# pca10040_sheet3_buttons_and_leds.net
KiCad netlist of a schematic drawn in Altium Designer
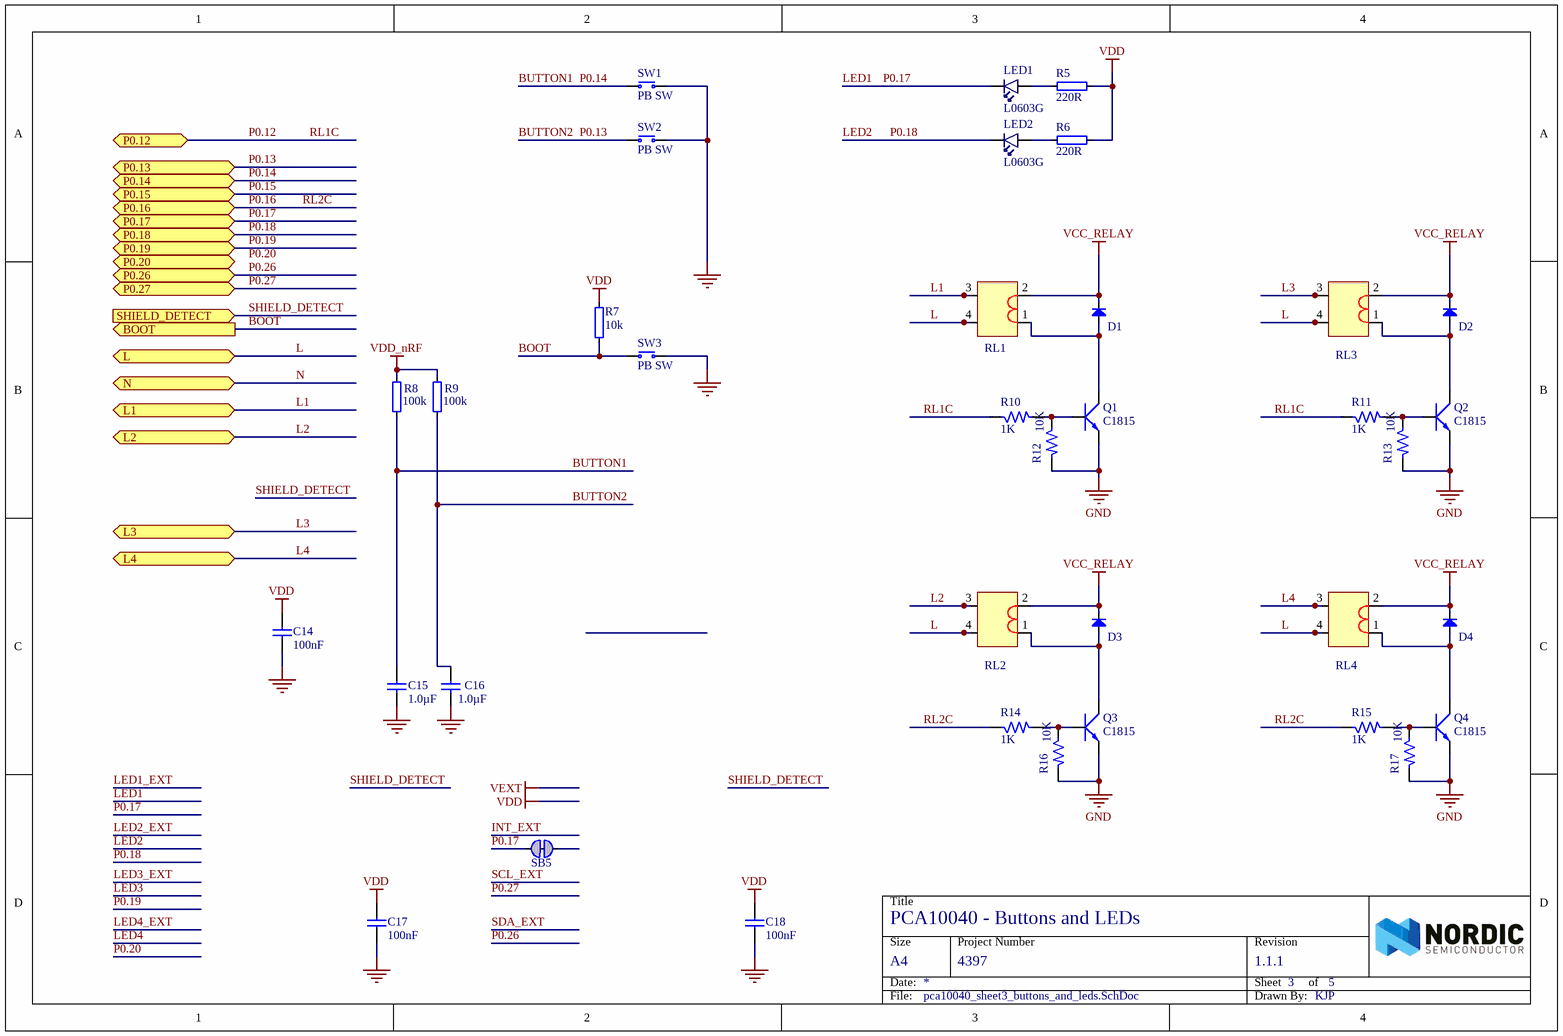
[diagram p0: pca10040_sheet3_buttons_and_leds.SchDoc]

(export (version "E")
  (design (tool "Eeschema 10.0.6"))
  (components
    (comp (ref "C14")
      (value "100nF")
      (footprint "CAPC1005X04L")
      (description "Capacitor, X7R, ±10%")
      (fields (field (name "PART NUMBER") "C0402-100n") (field (name "PUBLISHER") "Nordic Semiconductor"))
      (libsource (lib "Nordic Passive DB") (part "CAP"))
    )
    (comp (ref "C15")
      (value "1.0µF")
      (footprint "CAPC1608X06L")
      (description "Capacitor, X5R, ±5%")
      (fields (field (name "PART NUMBER") "C0402-1µ0") (field (name "PUBLISHER") "Nordic Semiconductor"))
      (libsource (lib "Nordic Passive DB") (part "CAP"))
    )
    (comp (ref "C16")
      (value "1.0µF")
      (footprint "CAPC1608X06L")
      (description "Capacitor, X5R, ±5%")
      (fields (field (name "PART NUMBER") "C0402-1µ0") (field (name "PUBLISHER") "Nordic Semiconductor"))
      (libsource (lib "Nordic Passive DB") (part "CAP"))
    )
    (comp (ref "C17")
      (value "100nF")
      (footprint "CAPC1005X04L")
      (description "Capacitor, X7R, ±10%")
      (fields (field (name "PART NUMBER") "C0402-100n") (field (name "PUBLISHER") "Nordic Semiconductor"))
      (libsource (lib "Nordic Passive DB") (part "CAP"))
    )
    (comp (ref "C18")
      (value "100nF")
      (footprint "CAPC1005X04L")
      (description "Capacitor, X7R, ±10%")
      (fields (field (name "PART NUMBER") "C0402-100n") (field (name "PUBLISHER") "Nordic Semiconductor"))
      (libsource (lib "Nordic Passive DB") (part "CAP"))
    )
    (comp (ref "D1")
      (value "Diode SMD")
      (footprint "DIO-SMD-123")
      (description "Default Diode")
      (fields (field (name "PUBLISHER") "Altium Limited"))
      (libsource (lib "LIBRARY") (part "Diode SMD"))
    )
    (comp (ref "D2")
      (value "Diode SMD")
      (footprint "DIO-SMD-123")
      (description "Default Diode")
      (fields (field (name "PUBLISHER") "Altium Limited"))
      (libsource (lib "LIBRARY") (part "Diode SMD"))
    )
    (comp (ref "D3")
      (value "Diode SMD")
      (footprint "DIO-SMD-123")
      (description "Default Diode")
      (fields (field (name "PUBLISHER") "Altium Limited"))
      (libsource (lib "LIBRARY") (part "Diode SMD"))
    )
    (comp (ref "D4")
      (value "Diode SMD")
      (footprint "DIO-SMD-123")
      (description "Default Diode")
      (fields (field (name "PUBLISHER") "Altium Limited"))
      (libsource (lib "LIBRARY") (part "Diode SMD"))
    )
    (comp (ref "LED1")
      (value "L0603G")
      (footprint "LED_0603_G")
      (description "LED SMARTLED GREEN 570NM 0603")
      (fields
        (field (name "PART NUMBER") "LG L29K Smartled Green")
        (field (name "MANUFACTURER") "Multicomp")
        (field (name "PUBLISHER") "Nordic Semiconductor")
      )
      (libsource (lib "Nordic Discrete DB") (part "D{colon}LED"))
    )
    (comp (ref "LED2")
      (value "L0603G")
      (footprint "LED_0603_G")
      (description "LED SMARTLED GREEN 570NM 0603")
      (fields
        (field (name "PART NUMBER") "LG L29K Smartled Green")
        (field (name "MANUFACTURER") "Multicomp")
        (field (name "PUBLISHER") "Nordic Semiconductor")
      )
      (libsource (lib "Nordic Discrete DB") (part "D{colon}LED"))
    )
    (comp (ref "Q1")
      (value "C1815")
      (footprint "SOT23B")
      (description "NPN 600mW, ECB")
      (libsource (lib "hatcatbietbay") (part "C1815"))
    )
    (comp (ref "Q2")
      (value "C1815")
      (footprint "SOT23B")
      (description "NPN 600mW, ECB")
      (libsource (lib "hatcatbietbay") (part "C1815"))
    )
    (comp (ref "Q3")
      (value "C1815")
      (footprint "SOT23B")
      (description "NPN 600mW, ECB")
      (libsource (lib "hatcatbietbay") (part "C1815"))
    )
    (comp (ref "Q4")
      (value "C1815")
      (footprint "SOT23B")
      (description "NPN 600mW, ECB")
      (libsource (lib "hatcatbietbay") (part "C1815"))
    )
    (comp (ref "R5")
      (value "220R")
      (footprint "0603")
      (description "Resistor, ±1%, 0.063W")
      (fields (field (name "PART NUMBER") "R0402-220") (field (name "PUBLISHER") "Nordic Semiconductor"))
      (libsource (lib "Nordic Passive DB") (part "RES_1"))
    )
    (comp (ref "R6")
      (value "220R")
      (footprint "0603")
      (description "Resistor, ±1%, 0.063W")
      (fields (field (name "PART NUMBER") "R0402-220") (field (name "PUBLISHER") "Nordic Semiconductor"))
      (libsource (lib "Nordic Passive DB") (part "RES_1"))
    )
    (comp (ref "R7")
      (value "10k")
      (footprint "RESC1005X04L")
      (description "Resistor, ±1%, 0.063W")
      (fields (field (name "PART NUMBER") "R0402-10k") (field (name "PUBLISHER") "Nordic Semiconductor"))
      (libsource (lib "Nordic Passive DB") (part "RES_1"))
    )
    (comp (ref "R8")
      (value "100k")
      (footprint "0603")
      (description "Resistor, ±1%, 0.063W")
      (fields (field (name "PART NUMBER") "R0402-100k") (field (name "PUBLISHER") "Nordic Semiconductor"))
      (libsource (lib "Nordic Passive DB") (part "RES_1"))
    )
    (comp (ref "R9")
      (value "100k")
      (footprint "0603")
      (description "Resistor, ±1%, 0.063W")
      (fields (field (name "PART NUMBER") "R0402-100k") (field (name "PUBLISHER") "Nordic Semiconductor"))
      (libsource (lib "Nordic Passive DB") (part "RES_1"))
    )
    (comp (ref "R10")
      (value "1K")
      (footprint "PcbLib1:0603")
      (description "Resistor 1/4W")
      (libsource (lib "hatcatbietbay") (part "R"))
    )
    (comp (ref "R11")
      (value "1K")
      (footprint "PcbLib1:0603")
      (description "Resistor 1/4W")
      (libsource (lib "hatcatbietbay") (part "R"))
    )
    (comp (ref "R12")
      (value "10K")
      (footprint "PcbLib1:0603")
      (description "Resistor 1/4W")
      (libsource (lib "hatcatbietbay") (part "R"))
    )
    (comp (ref "R13")
      (value "10K")
      (footprint "PcbLib1:0603")
      (description "Resistor 1/4W")
      (libsource (lib "hatcatbietbay") (part "R"))
    )
    (comp (ref "R14")
      (value "1K")
      (footprint "PcbLib1:0603")
      (description "Resistor 1/4W")
      (libsource (lib "hatcatbietbay") (part "R"))
    )
    (comp (ref "R15")
      (value "1K")
      (footprint "PcbLib1:0603")
      (description "Resistor 1/4W")
      (libsource (lib "hatcatbietbay") (part "R"))
    )
    (comp (ref "R16")
      (value "10K")
      (footprint "PcbLib1:0603")
      (description "Resistor 1/4W")
      (libsource (lib "hatcatbietbay") (part "R"))
    )
    (comp (ref "R17")
      (value "10K")
      (footprint "PcbLib1:0603")
      (description "Resistor 1/4W")
      (libsource (lib "hatcatbietbay") (part "R"))
    )
    (comp (ref "RL1")
      (value "Component_1")
      (footprint "AZ7705")
      (libsource (lib "Zettler") (part "Component_1"))
    )
    (comp (ref "RL2")
      (value "Component_1")
      (footprint "AZ7705")
      (libsource (lib "Zettler") (part "Component_1"))
    )
    (comp (ref "RL3")
      (value "Component_1")
      (footprint "AZ7705")
      (libsource (lib "Zettler") (part "Component_1"))
    )
    (comp (ref "RL4")
      (value "Component_1")
      (footprint "AZ7705")
      (libsource (lib "Zettler") (part "Component_1"))
    )
    (comp (ref "SB5")
      (value "Solderbridge")
      (footprint "Solderbridge_Shorted")
      (description "Shorted Solderbridge")
      (fields
        (field (name "PART NUMBER") "Solderbridge Shorted")
        (field (name "PUBLISHER") "Nordic Semiconductor")
      )
      (libsource (lib "Nordic Passive DB") (part "SOLDERBRIDGE_SHORTED"))
    )
    (comp (ref "SW1")
      (value "PB SW")
      (footprint "D2FC-F-7N")
      (description "Tactile Switch, SPNO, SMD, 160gf, 6.2x6.3x2.5mm")
      (fields
        (field (name "PART NUMBER") "Switch-PB-6.2x6.3mm-SMD")
        (field (name "MANUFACTURER") "Dailywell")
        (field (name "PUBLISHER") "Nordic Semiconductor")
      )
      (libsource (lib "Nordic Discrete DB") (part "SW-PB"))
    )
    (comp (ref "SW2")
      (value "PB SW")
      (footprint "D2FC-F-7N")
      (description "Tactile Switch, SPNO, SMD, 160gf, 6.2x6.3x2.5mm")
      (fields
        (field (name "PART NUMBER") "Switch-PB-6.2x6.3mm-SMD")
        (field (name "MANUFACTURER") "Dailywell")
        (field (name "PUBLISHER") "Nordic Semiconductor")
      )
      (libsource (lib "Nordic Discrete DB") (part "SW-PB"))
    )
    (comp (ref "SW3")
      (value "PB SW")
      (footprint "Switch-PB-6.2x6.3mm-SMD")
      (description "Tactile Switch, SPNO, SMD, 160gf, 6.2x6.3x2.5mm")
      (fields
        (field (name "PART NUMBER") "Switch-PB-6.2x6.3mm-SMD")
        (field (name "MANUFACTURER") "Dailywell")
        (field (name "PUBLISHER") "Nordic Semiconductor")
      )
      (libsource (lib "Nordic Discrete DB") (part "SW-PB"))
    )
  )
  (nets
    (net (code "1") (name "/BOOT") (class "Default")
      (node (ref "R7") (pin "1") (pinfunction "1_1") (pintype "passive"))
      (node (ref "SW3") (pin "2") (pinfunction "COM_2") (pintype "passive"))
    )
    (net (code "2") (name "/BUTTON1") (class "Default")
      (node (ref "C15") (pin "1") (pinfunction "1_1") (pintype "passive"))
      (node (ref "R8") (pin "1") (pinfunction "1_1") (pintype "passive"))
      (node (ref "SW1") (pin "2") (pinfunction "COM_2") (pintype "passive"))
    )
    (net (code "3") (name "/BUTTON2") (class "Default")
      (node (ref "C16") (pin "2") (pinfunction "2_2") (pintype "passive"))
      (node (ref "R9") (pin "1") (pinfunction "1_1") (pintype "passive"))
      (node (ref "SW2") (pin "2") (pinfunction "COM_2") (pintype "passive"))
    )
    (net (code "5") (name "/L") (class "Default")
      (node (ref "RL1") (pin "4") (pintype "passive"))
      (node (ref "RL2") (pin "4") (pintype "passive"))
      (node (ref "RL3") (pin "4") (pintype "passive"))
      (node (ref "RL4") (pin "4") (pintype "passive"))
    )
    (net (code "6") (name "/L1") (class "Default") (node (ref "RL1") (pin "3") (pintype "passive")))
    (net (code "7") (name "/L2") (class "Default") (node (ref "RL2") (pin "3") (pintype "passive")))
    (net (code "8") (name "/L3") (class "Default") (node (ref "RL3") (pin "3") (pintype "passive")))
    (net (code "9") (name "/L4") (class "Default") (node (ref "RL4") (pin "3") (pintype "passive")))
    (net (code "10") (name "/LED1") (class "Default")
      (node (ref "LED1") (pin "1") (pinfunction "C_1") (pintype "passive"))
      (node (ref "SB5") (pin "1") (pinfunction "0_1") (pintype "passive"))
    )
    (net (code "12") (name "/LED2") (class "Default")
      (node (ref "LED2") (pin "1") (pinfunction "C_1") (pintype "passive"))
    )
    (net (code "19") (name "/P0.12") (class "Default")
      (node (ref "R10") (pin "1") (pinfunction "1_1") (pintype "passive"))
      (node (ref "R11") (pin "1") (pinfunction "1_1") (pintype "passive"))
    )
    (net (code "21") (name "/P0.16") (class "Default")
      (node (ref "R14") (pin "1") (pinfunction "1_1") (pintype "passive"))
      (node (ref "R15") (pin "1") (pinfunction "1_1") (pintype "passive"))
    )
    (net (code "29") (name "GND") (class "Default")
      (node (ref "C14") (pin "1") (pinfunction "1_1") (pintype "passive"))
      (node (ref "C15") (pin "2") (pinfunction "2_2") (pintype "passive"))
      (node (ref "C16") (pin "1") (pinfunction "1_1") (pintype "passive"))
      (node (ref "C17") (pin "1") (pinfunction "1_1") (pintype "passive"))
      (node (ref "C18") (pin "1") (pinfunction "1_1") (pintype "passive"))
      (node (ref "Q1") (pin "3") (pinfunction "E_3") (pintype "passive"))
      (node (ref "Q2") (pin "3") (pinfunction "E_3") (pintype "passive"))
      (node (ref "Q3") (pin "3") (pinfunction "E_3") (pintype "passive"))
      (node (ref "Q4") (pin "3") (pinfunction "E_3") (pintype "passive"))
      (node (ref "R12") (pin "2") (pinfunction "2_2") (pintype "passive"))
      (node (ref "R13") (pin "2") (pinfunction "2_2") (pintype "passive"))
      (node (ref "R16") (pin "2") (pinfunction "2_2") (pintype "passive"))
      (node (ref "R17") (pin "2") (pinfunction "2_2") (pintype "passive"))
      (node (ref "SW1") (pin "1") (pinfunction "N.O_1") (pintype "passive"))
      (node (ref "SW2") (pin "1") (pinfunction "N.O_1") (pintype "passive"))
      (node (ref "SW3") (pin "1") (pinfunction "N.O_1") (pintype "passive"))
    )
    (net (code "30") (name "Net-(D1-A)") (class "Default")
      (node (ref "D1") (pin "1") (pinfunction "A_1") (pintype "passive"))
      (node (ref "Q1") (pin "2") (pinfunction "C_2") (pintype "passive"))
      (node (ref "RL1") (pin "1") (pintype "passive"))
    )
    (net (code "31") (name "Net-(D2-A)") (class "Default")
      (node (ref "D2") (pin "1") (pinfunction "A_1") (pintype "passive"))
      (node (ref "Q2") (pin "2") (pinfunction "C_2") (pintype "passive"))
      (node (ref "RL3") (pin "1") (pintype "passive"))
    )
    (net (code "32") (name "Net-(D3-A)") (class "Default")
      (node (ref "D3") (pin "1") (pinfunction "A_1") (pintype "passive"))
      (node (ref "Q3") (pin "2") (pinfunction "C_2") (pintype "passive"))
      (node (ref "RL2") (pin "1") (pintype "passive"))
    )
    (net (code "33") (name "Net-(D4-A)") (class "Default")
      (node (ref "D4") (pin "1") (pinfunction "A_1") (pintype "passive"))
      (node (ref "Q4") (pin "2") (pinfunction "C_2") (pintype "passive"))
      (node (ref "RL4") (pin "1") (pintype "passive"))
    )
    (net (code "34") (name "Net-(LED1-A)") (class "Default")
      (node (ref "LED1") (pin "2") (pinfunction "A_2") (pintype "passive"))
      (node (ref "R5") (pin "1") (pinfunction "1_1") (pintype "passive"))
    )
    (net (code "35") (name "Net-(LED2-A)") (class "Default")
      (node (ref "LED2") (pin "2") (pinfunction "A_2") (pintype "passive"))
      (node (ref "R6") (pin "1") (pinfunction "1_1") (pintype "passive"))
    )
    (net (code "36") (name "Net-(Q1-B)") (class "Default")
      (node (ref "Q1") (pin "1") (pinfunction "B_1") (pintype "passive"))
      (node (ref "R10") (pin "2") (pinfunction "2_2") (pintype "passive"))
      (node (ref "R12") (pin "1") (pinfunction "1_1") (pintype "passive"))
    )
    (net (code "37") (name "Net-(Q2-B)") (class "Default")
      (node (ref "Q2") (pin "1") (pinfunction "B_1") (pintype "passive"))
      (node (ref "R11") (pin "2") (pinfunction "2_2") (pintype "passive"))
      (node (ref "R13") (pin "1") (pinfunction "1_1") (pintype "passive"))
    )
    (net (code "38") (name "Net-(Q3-B)") (class "Default")
      (node (ref "Q3") (pin "1") (pinfunction "B_1") (pintype "passive"))
      (node (ref "R14") (pin "2") (pinfunction "2_2") (pintype "passive"))
      (node (ref "R16") (pin "1") (pinfunction "1_1") (pintype "passive"))
    )
    (net (code "39") (name "Net-(Q4-B)") (class "Default")
      (node (ref "Q4") (pin "1") (pinfunction "B_1") (pintype "passive"))
      (node (ref "R15") (pin "2") (pinfunction "2_2") (pintype "passive"))
      (node (ref "R17") (pin "1") (pinfunction "1_1") (pintype "passive"))
    )
    (net (code "40") (name "VCC_RELAY") (class "Default")
      (node (ref "D1") (pin "2") (pinfunction "K_2") (pintype "passive"))
      (node (ref "D2") (pin "2") (pinfunction "K_2") (pintype "passive"))
      (node (ref "D3") (pin "2") (pinfunction "K_2") (pintype "passive"))
      (node (ref "D4") (pin "2") (pinfunction "K_2") (pintype "passive"))
      (node (ref "RL1") (pin "2") (pintype "passive"))
      (node (ref "RL2") (pin "2") (pintype "passive"))
      (node (ref "RL3") (pin "2") (pintype "passive"))
      (node (ref "RL4") (pin "2") (pintype "passive"))
    )
    (net (code "41") (name "VDD") (class "Default")
      (node (ref "C14") (pin "2") (pinfunction "2_2") (pintype "passive"))
      (node (ref "C17") (pin "2") (pinfunction "2_2") (pintype "passive"))
      (node (ref "C18") (pin "2") (pinfunction "2_2") (pintype "passive"))
      (node (ref "R5") (pin "2") (pinfunction "2_2") (pintype "passive"))
      (node (ref "R6") (pin "2") (pinfunction "2_2") (pintype "passive"))
      (node (ref "R7") (pin "2") (pinfunction "2_2") (pintype "passive"))
    )
    (net (code "42") (name "VDD_nRF") (class "Default")
      (node (ref "R8") (pin "2") (pinfunction "2_2") (pintype "passive"))
      (node (ref "R9") (pin "2") (pinfunction "2_2") (pintype "passive"))
    )
    (net (code "44") (name "unconnected-(SB5-1-Pad2)") (class "Default")
      (node (ref "SB5") (pin "2") (pinfunction "1_2") (pintype "passive"))
    )
  )
)
